# Rocket_End_Relays.net
KiCad netlist of a schematic drawn in EAGLE
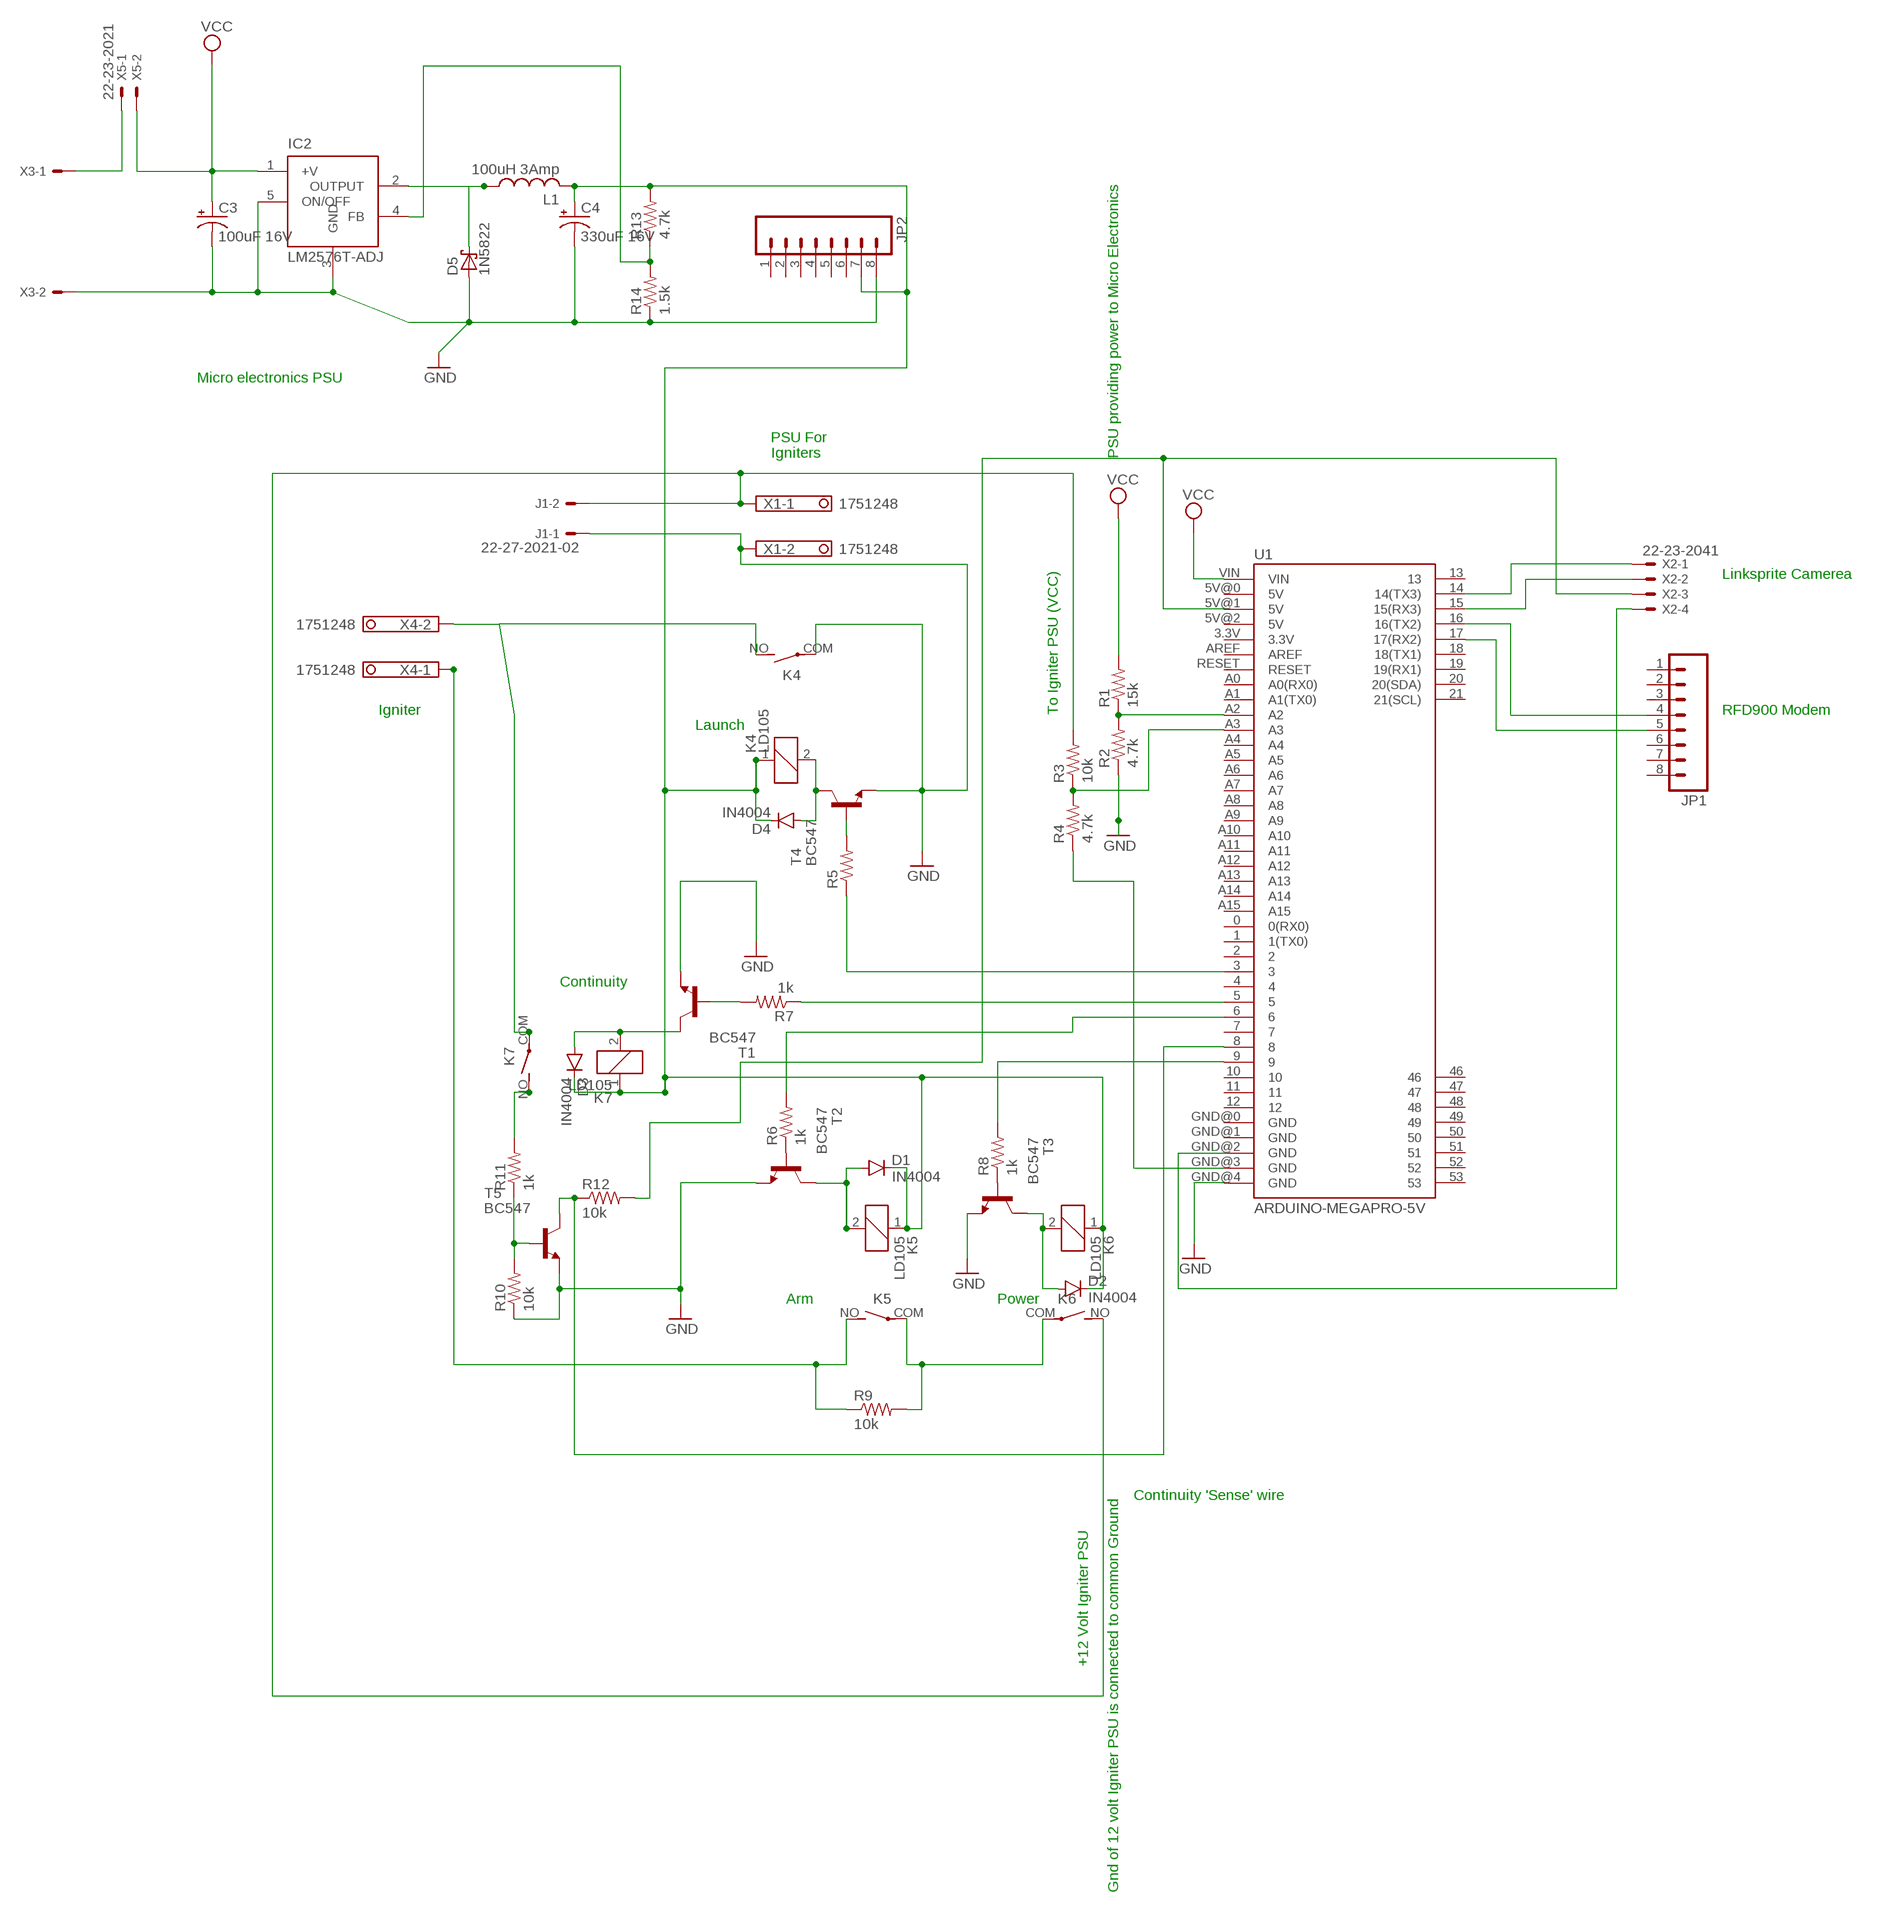
[diagram p0: schematic, sheet 1]

(export (version "E")
  (design (tool "Eeschema 10.0.6"))
  (components
    (comp (ref "C3")
      (value "100uF 16V")
      (footprint "eagle-import:E2-4")
      (libsource (lib "eagle-import") (part "CPOL-USE2-4"))
    )
    (comp (ref "C4")
      (value "330uF 16V")
      (footprint "eagle-import:E2-4")
      (libsource (lib "eagle-import") (part "CPOL-USE2-4"))
    )
    (comp (ref "D1")
      (value "IN4004")
      (footprint "eagle-import:DIODE-1N4148")
      (libsource (lib "eagle-import") (part "DIODE1N4148"))
    )
    (comp (ref "D2")
      (value "IN4004")
      (footprint "eagle-import:DIODE-1N4148")
      (libsource (lib "eagle-import") (part "DIODE1N4148"))
    )
    (comp (ref "D3")
      (value "IN4004")
      (footprint "eagle-import:DIODE-1N4148")
      (libsource (lib "eagle-import") (part "DIODE1N4148"))
    )
    (comp (ref "D4")
      (value "IN4004")
      (footprint "eagle-import:DIODE-1N4148")
      (libsource (lib "eagle-import") (part "DIODE1N4148"))
    )
    (comp (ref "D5")
      (value "1N5822")
      (footprint "eagle-import:C4111-15")
      (libsource (lib "eagle-import") (part "1N5908"))
    )
    (comp (ref "IC2")
      (value "LM2576T-ADJ")
      (footprint "eagle-import:TO220-5")
      (libsource (lib "eagle-import") (part "LM2576T-ADJ"))
    )
    (comp (ref "J1")
      (value "22-27-2021-02")
      (footprint "eagle-import:6410-02")
      (libsource (lib "eagle-import") (part "22-?-0227-2021"))
    )
    (comp (ref "JP1")
      (value "M08")
      (footprint "eagle-import:1X08_ROUND")
      (libsource (lib "eagle-import") (part "M08"))
    )
    (comp (ref "JP2")
      (value "M08")
      (footprint "eagle-import:1X08_ROUND")
      (libsource (lib "eagle-import") (part "M08"))
    )
    (comp (ref "K4")
      (value "LD105")
      (footprint "eagle-import:LD")
      (libsource (lib "eagle-import") (part "LD?105"))
    )
    (comp (ref "K5")
      (value "LD105")
      (footprint "eagle-import:LD")
      (libsource (lib "eagle-import") (part "LD?105"))
    )
    (comp (ref "K6")
      (value "LD105")
      (footprint "eagle-import:LD")
      (libsource (lib "eagle-import") (part "LD?105"))
    )
    (comp (ref "K7")
      (value "LD105")
      (footprint "eagle-import:LD")
      (libsource (lib "eagle-import") (part "LD?105"))
    )
    (comp (ref "L1")
      (value "100uH 3Amp")
      (footprint "eagle-import:TJ4-U1")
      (libsource (lib "eagle-import") (part "L-USTJ4-U1"))
    )
    (comp (ref "R1")
      (value "15k")
      (footprint "eagle-import:0204_7")
      (libsource (lib "eagle-import") (part "R-US_0204/7"))
    )
    (comp (ref "R2")
      (value "4.7k")
      (footprint "eagle-import:0204_7")
      (libsource (lib "eagle-import") (part "R-US_0204/7"))
    )
    (comp (ref "R3")
      (value "10k")
      (footprint "eagle-import:0204_7")
      (libsource (lib "eagle-import") (part "R-US_0204/7"))
    )
    (comp (ref "R4")
      (value "4.7k")
      (footprint "eagle-import:0204_7")
      (libsource (lib "eagle-import") (part "R-US_0204/7"))
    )
    (comp (ref "R5")
      (value "R-US_0204/7")
      (footprint "eagle-import:0204_7")
      (libsource (lib "eagle-import") (part "resistor_R-US_0204/7"))
    )
    (comp (ref "R6")
      (value "1k")
      (footprint "eagle-import:0204_7")
      (libsource (lib "eagle-import") (part "resistor_R-US_0204/7"))
    )
    (comp (ref "R7")
      (value "1k")
      (footprint "eagle-import:0204_7")
      (libsource (lib "eagle-import") (part "resistor_R-US_0204/7"))
    )
    (comp (ref "R8")
      (value "1k")
      (footprint "eagle-import:0204_7")
      (libsource (lib "eagle-import") (part "resistor_R-US_0204/7"))
    )
    (comp (ref "R9")
      (value "10k")
      (footprint "eagle-import:0204_7")
      (libsource (lib "eagle-import") (part "R-US_0204/7"))
    )
    (comp (ref "R10")
      (value "10k")
      (footprint "eagle-import:0207_7")
      (libsource (lib "eagle-import") (part "R-US_0207/7"))
    )
    (comp (ref "R11")
      (value "1k")
      (footprint "eagle-import:0207_12")
      (libsource (lib "eagle-import") (part "resistor_R-US_0207/12"))
    )
    (comp (ref "R12")
      (value "10k")
      (footprint "eagle-import:0204_7")
      (libsource (lib "eagle-import") (part "resistor_R-US_0204/7"))
    )
    (comp (ref "R13")
      (value "4.7k")
      (footprint "eagle-import:0204V")
      (libsource (lib "eagle-import") (part "resistor_R-US_0204/2V"))
    )
    (comp (ref "R14")
      (value "1.5k")
      (footprint "eagle-import:0207_7")
      (libsource (lib "eagle-import") (part "resistor_R-US_0207/7"))
    )
    (comp (ref "T1")
      (value "BC547")
      (footprint "eagle-import:TO92")
      (libsource (lib "eagle-import") (part "transistor-neu-to92_BC547"))
    )
    (comp (ref "T2")
      (value "BC547")
      (footprint "eagle-import:TO92")
      (libsource (lib "eagle-import") (part "transistor-neu-to92_BC547"))
    )
    (comp (ref "T3")
      (value "BC547")
      (footprint "eagle-import:TO92")
      (libsource (lib "eagle-import") (part "transistor-neu-to92_BC547"))
    )
    (comp (ref "T4")
      (value "BC547")
      (footprint "eagle-import:TO92")
      (libsource (lib "eagle-import") (part "transistor-neu-to92_BC547"))
    )
    (comp (ref "T5")
      (value "BC547")
      (footprint "eagle-import:TO92")
      (libsource (lib "eagle-import") (part "BC547"))
    )
    (comp (ref "U1")
      (value "ARDUINO-MEGAPRO-5V")
      (footprint "eagle-import:ARDUINO_MEGA-PRO-5V")
      (libsource (lib "eagle-import") (part "ARDUINO-MEGAPRO-5V"))
    )
    (comp (ref "X1")
      (value "1751248")
      (footprint "eagle-import:1751248")
      (libsource (lib "eagle-import") (part "1751248"))
    )
    (comp (ref "X2")
      (value "22-23-2041")
      (footprint "eagle-import:22-23-2041")
      (fields (field (name "MF") "MOLEX"))
      (libsource (lib "eagle-import") (part "22-23-2041"))
    )
    (comp (ref "X3")
      (value "22-23-2021")
      (footprint "eagle-import:22-23-2021")
      (fields (field (name "MF") "MOLEX"))
      (libsource (lib "eagle-import") (part "22-23-2021"))
    )
    (comp (ref "X4")
      (value "1751248")
      (footprint "eagle-import:1751248")
      (libsource (lib "eagle-import") (part "1751248"))
    )
    (comp (ref "X5")
      (value "22-23-2021")
      (footprint "eagle-import:22-23-2021")
      (fields (field (name "MF") "MOLEX"))
      (libsource (lib "eagle-import") (part "22-23-2021"))
    )
  )
  (nets
    (net (code "1") (name "GND") (class "Default")
      (node (ref "C3") (pin "-") (pinfunction "-_-") (pintype "passive"))
      (node (ref "C4") (pin "-") (pinfunction "-_-") (pintype "passive"))
      (node (ref "D5") (pin "A") (pinfunction "A_A") (pintype "passive"))
      (node (ref "IC2") (pin "3") (pinfunction "GND_3") (pintype "power_in"))
      (node (ref "IC2") (pin "5") (pinfunction "ON/OFF_5") (pintype "input"))
      (node (ref "J1") (pin "1") (pinfunction "S_1") (pintype "passive"))
      (node (ref "JP2") (pin "8") (pinfunction "8_8") (pintype "passive"))
      (node (ref "K4") (pin "COM") (pinfunction "P_COM") (pintype "passive"))
      (node (ref "R10") (pin "1") (pinfunction "1_1") (pintype "passive"))
      (node (ref "R14") (pin "1") (pinfunction "1_1") (pintype "passive"))
      (node (ref "R2") (pin "1") (pinfunction "1_1") (pintype "passive"))
      (node (ref "T1") (pin "1") (pinfunction "E_1") (pintype "passive"))
      (node (ref "T2") (pin "1") (pinfunction "E_1") (pintype "passive"))
      (node (ref "T3") (pin "1") (pinfunction "E_1") (pintype "passive"))
      (node (ref "T4") (pin "1") (pinfunction "E_1") (pintype "passive"))
      (node (ref "T5") (pin "1") (pinfunction "E_1") (pintype "passive"))
      (node (ref "U1") (pin "GND@4") (pinfunction "GND_GND@4") (pintype "bidirectional"))
      (node (ref "X1") (pin "2") (pinfunction "K_2") (pintype "passive"))
      (node (ref "X3") (pin "2") (pinfunction "S_2") (pintype "passive"))
    )
    (net (code "2") (name "Net-(C4-Pad+)") (class "Default")
      (node (ref "C4") (pin "+") (pinfunction "+_+") (pintype "passive"))
      (node (ref "D1") (pin "C") (pinfunction "C_C") (pintype "passive"))
      (node (ref "D2") (pin "C") (pinfunction "C_C") (pintype "passive"))
      (node (ref "D3") (pin "C") (pinfunction "C_C") (pintype "passive"))
      (node (ref "D4") (pin "C") (pinfunction "C_C") (pintype "passive"))
      (node (ref "JP2") (pin "7") (pinfunction "7_7") (pintype "passive"))
      (node (ref "K4") (pin "1") (pinfunction "1_1") (pintype "passive"))
      (node (ref "K5") (pin "1") (pinfunction "1_1") (pintype "passive"))
      (node (ref "K6") (pin "1") (pinfunction "1_1") (pintype "passive"))
      (node (ref "K7") (pin "1") (pinfunction "1_1") (pintype "passive"))
      (node (ref "L1") (pin "2") (pinfunction "2_2") (pintype "passive"))
      (node (ref "R13") (pin "2") (pinfunction "2_2") (pintype "passive"))
    )
    (net (code "3") (name "Net-(IC2-FB)") (class "Default")
      (node (ref "IC2") (pin "4") (pinfunction "FB_4") (pintype "input"))
      (node (ref "R13") (pin "1") (pinfunction "1_1") (pintype "passive"))
      (node (ref "R14") (pin "2") (pinfunction "2_2") (pintype "passive"))
    )
    (net (code "4") (name "Net-(IC2-OUTPUT)") (class "Default")
      (node (ref "D5") (pin "C") (pinfunction "C_C") (pintype "passive"))
      (node (ref "IC2") (pin "2") (pinfunction "OUTPUT_2") (pintype "output"))
      (node (ref "L1") (pin "1") (pinfunction "1_1") (pintype "passive"))
    )
    (net (code "5") (name "Net-(J1B-S)") (class "Default")
      (node (ref "J1") (pin "2") (pinfunction "S_2") (pintype "passive"))
      (node (ref "K6") (pin "NO") (pinfunction "S_NO") (pintype "passive"))
      (node (ref "R3") (pin "2") (pinfunction "2_2") (pintype "passive"))
      (node (ref "X1") (pin "1") (pinfunction "K_1") (pintype "passive"))
    )
    (net (code "6") (name "Net-(K4B-S)") (class "Default")
      (node (ref "K4") (pin "NO") (pinfunction "S_NO") (pintype "passive"))
      (node (ref "K7") (pin "COM") (pinfunction "P_COM") (pintype "passive"))
      (node (ref "X4") (pin "2") (pinfunction "K_2") (pintype "passive"))
    )
    (net (code "7") (name "Net-(K5B-P)") (class "Default")
      (node (ref "K5") (pin "COM") (pinfunction "P_COM") (pintype "passive"))
      (node (ref "K6") (pin "COM") (pinfunction "P_COM") (pintype "passive"))
      (node (ref "R9") (pin "2") (pinfunction "2_2") (pintype "passive"))
    )
    (net (code "8") (name "Net-(K5B-S)") (class "Default")
      (node (ref "K5") (pin "NO") (pinfunction "S_NO") (pintype "passive"))
      (node (ref "R9") (pin "1") (pinfunction "1_1") (pintype "passive"))
      (node (ref "X4") (pin "1") (pinfunction "K_1") (pintype "passive"))
    )
    (net (code "9") (name "Net-(K7B-S)") (class "Default")
      (node (ref "K7") (pin "NO") (pinfunction "S_NO") (pintype "passive"))
      (node (ref "R11") (pin "2") (pinfunction "2_2") (pintype "passive"))
    )
    (net (code "10") (name "Net-(R1-Pad1)") (class "Default")
      (node (ref "R1") (pin "1") (pinfunction "1_1") (pintype "passive"))
      (node (ref "R2") (pin "2") (pinfunction "2_2") (pintype "passive"))
      (node (ref "U1") (pin "A2") (pinfunction "A2_A2") (pintype "bidirectional"))
    )
    (net (code "11") (name "Net-(R3-Pad1)") (class "Default")
      (node (ref "R3") (pin "1") (pinfunction "1_1") (pintype "passive"))
      (node (ref "R4") (pin "2") (pinfunction "2_2") (pintype "passive"))
      (node (ref "U1") (pin "A3") (pinfunction "A3_A3") (pintype "bidirectional"))
    )
    (net (code "12") (name "Net-(R4-Pad1)") (class "Default")
      (node (ref "R4") (pin "1") (pinfunction "1_1") (pintype "passive"))
      (node (ref "U1") (pin "GND@3") (pinfunction "GND_GND@3") (pintype "bidirectional"))
    )
    (net (code "13") (name "Net-(R5-Pad1)") (class "Default")
      (node (ref "R5") (pin "1") (pinfunction "1_1") (pintype "passive"))
      (node (ref "U1") (pin "3") (pinfunction "3_3") (pintype "bidirectional"))
    )
    (net (code "14") (name "Net-(R6-Pad2)") (class "Default")
      (node (ref "R6") (pin "2") (pinfunction "2_2") (pintype "passive"))
      (node (ref "U1") (pin "6") (pinfunction "6_6") (pintype "bidirectional"))
    )
    (net (code "15") (name "Net-(R7-Pad1)") (class "Default")
      (node (ref "R7") (pin "1") (pinfunction "1_1") (pintype "passive"))
      (node (ref "U1") (pin "5") (pinfunction "5_5") (pintype "bidirectional"))
    )
    (net (code "16") (name "Net-(R8-Pad2)") (class "Default")
      (node (ref "R8") (pin "2") (pinfunction "2_2") (pintype "passive"))
      (node (ref "U1") (pin "9") (pinfunction "9_9") (pintype "bidirectional"))
    )
    (net (code "17") (name "Net-(T1-B)") (class "Default")
      (node (ref "R7") (pin "2") (pinfunction "2_2") (pintype "passive"))
      (node (ref "T1") (pin "2") (pinfunction "B_2") (pintype "passive"))
    )
    (net (code "18") (name "Net-(T1-C)") (class "Default")
      (node (ref "D3") (pin "A") (pinfunction "A_A") (pintype "passive"))
      (node (ref "K7") (pin "2") (pinfunction "2_2") (pintype "passive"))
      (node (ref "T1") (pin "3") (pinfunction "C_3") (pintype "passive"))
    )
    (net (code "19") (name "Net-(T2-B)") (class "Default")
      (node (ref "R6") (pin "1") (pinfunction "1_1") (pintype "passive"))
      (node (ref "T2") (pin "2") (pinfunction "B_2") (pintype "passive"))
    )
    (net (code "20") (name "Net-(T2-C)") (class "Default")
      (node (ref "D1") (pin "A") (pinfunction "A_A") (pintype "passive"))
      (node (ref "K5") (pin "2") (pinfunction "2_2") (pintype "passive"))
      (node (ref "T2") (pin "3") (pinfunction "C_3") (pintype "passive"))
    )
    (net (code "21") (name "Net-(T3-B)") (class "Default")
      (node (ref "R8") (pin "1") (pinfunction "1_1") (pintype "passive"))
      (node (ref "T3") (pin "2") (pinfunction "B_2") (pintype "passive"))
    )
    (net (code "22") (name "Net-(T3-C)") (class "Default")
      (node (ref "D2") (pin "A") (pinfunction "A_A") (pintype "passive"))
      (node (ref "K6") (pin "2") (pinfunction "2_2") (pintype "passive"))
      (node (ref "T3") (pin "3") (pinfunction "C_3") (pintype "passive"))
    )
    (net (code "23") (name "Net-(T4-B)") (class "Default")
      (node (ref "R5") (pin "2") (pinfunction "2_2") (pintype "passive"))
      (node (ref "T4") (pin "2") (pinfunction "B_2") (pintype "passive"))
    )
    (net (code "24") (name "Net-(T4-C)") (class "Default")
      (node (ref "D4") (pin "A") (pinfunction "A_A") (pintype "passive"))
      (node (ref "K4") (pin "2") (pinfunction "2_2") (pintype "passive"))
      (node (ref "T4") (pin "3") (pinfunction "C_3") (pintype "passive"))
    )
    (net (code "25") (name "Net-(T5-B)") (class "Default")
      (node (ref "R10") (pin "2") (pinfunction "2_2") (pintype "passive"))
      (node (ref "R11") (pin "1") (pinfunction "1_1") (pintype "passive"))
      (node (ref "T5") (pin "2") (pinfunction "B_2") (pintype "passive"))
    )
    (net (code "26") (name "Net-(T5-C)") (class "Default")
      (node (ref "R12") (pin "1") (pinfunction "1_1") (pintype "passive"))
      (node (ref "T5") (pin "3") (pinfunction "C_3") (pintype "passive"))
      (node (ref "U1") (pin "8") (pinfunction "8_8") (pintype "bidirectional"))
    )
    (net (code "27") (name "Net-(U1-14(TX3))") (class "Default")
      (node (ref "U1") (pin "14") (pinfunction "14(TX3)_14") (pintype "bidirectional"))
      (node (ref "X2") (pin "1") (pinfunction "S_1") (pintype "passive"))
    )
    (net (code "28") (name "Net-(U1-15(RX3))") (class "Default")
      (node (ref "U1") (pin "15") (pinfunction "15(RX3)_15") (pintype "bidirectional"))
      (node (ref "X2") (pin "2") (pinfunction "S_2") (pintype "passive"))
    )
    (net (code "29") (name "Net-(U1-16(TX2))") (class "Default")
      (node (ref "JP1") (pin "4") (pinfunction "4_4") (pintype "passive"))
      (node (ref "U1") (pin "16") (pinfunction "16(TX2)_16") (pintype "bidirectional"))
    )
    (net (code "30") (name "Net-(U1-17(RX2))") (class "Default")
      (node (ref "JP1") (pin "5") (pinfunction "5_5") (pintype "passive"))
      (node (ref "U1") (pin "17") (pinfunction "17(RX2)_17") (pintype "bidirectional"))
    )
    (net (code "31") (name "Net-(X2C-S)") (class "Default")
      (node (ref "R12") (pin "2") (pinfunction "2_2") (pintype "passive"))
      (node (ref "U1") (pin "5V@1") (pinfunction "5V_5V@1") (pintype "bidirectional"))
      (node (ref "X2") (pin "3") (pinfunction "S_3") (pintype "passive"))
    )
    (net (code "32") (name "Net-(X2D-S)") (class "Default")
      (node (ref "U1") (pin "GND@2") (pinfunction "GND_GND@2") (pintype "bidirectional"))
      (node (ref "X2") (pin "4") (pinfunction "S_4") (pintype "passive"))
    )
    (net (code "33") (name "Net-(X3A-S)") (class "Default")
      (node (ref "X3") (pin "1") (pinfunction "S_1") (pintype "passive"))
      (node (ref "X5") (pin "1") (pinfunction "S_1") (pintype "passive"))
    )
    (net (code "34") (name "VCC") (class "Default")
      (node (ref "C3") (pin "+") (pinfunction "+_+") (pintype "passive"))
      (node (ref "IC2") (pin "1") (pinfunction "+V_1") (pintype "power_in"))
      (node (ref "R1") (pin "2") (pinfunction "2_2") (pintype "passive"))
      (node (ref "U1") (pin "VIN") (pinfunction "VIN_VIN") (pintype "bidirectional"))
      (node (ref "X5") (pin "2") (pinfunction "S_2") (pintype "passive"))
    )
    (net (code "35") (name "unconnected-(JP1-Pad1)") (class "Default")
      (node (ref "JP1") (pin "1") (pinfunction "1_1") (pintype "passive"))
    )
    (net (code "36") (name "unconnected-(JP1-Pad2)") (class "Default")
      (node (ref "JP1") (pin "2") (pinfunction "2_2") (pintype "passive"))
    )
    (net (code "37") (name "unconnected-(JP1-Pad3)") (class "Default")
      (node (ref "JP1") (pin "3") (pinfunction "3_3") (pintype "passive"))
    )
    (net (code "38") (name "unconnected-(JP1-Pad6)") (class "Default")
      (node (ref "JP1") (pin "6") (pinfunction "6_6") (pintype "passive"))
    )
    (net (code "39") (name "unconnected-(JP1-Pad7)") (class "Default")
      (node (ref "JP1") (pin "7") (pinfunction "7_7") (pintype "passive"))
    )
    (net (code "40") (name "unconnected-(JP1-Pad8)") (class "Default")
      (node (ref "JP1") (pin "8") (pinfunction "8_8") (pintype "passive"))
    )
    (net (code "41") (name "unconnected-(JP2-Pad1)") (class "Default")
      (node (ref "JP2") (pin "1") (pinfunction "1_1") (pintype "passive"))
    )
    (net (code "42") (name "unconnected-(JP2-Pad2)") (class "Default")
      (node (ref "JP2") (pin "2") (pinfunction "2_2") (pintype "passive"))
    )
    (net (code "43") (name "unconnected-(JP2-Pad3)") (class "Default")
      (node (ref "JP2") (pin "3") (pinfunction "3_3") (pintype "passive"))
    )
    (net (code "44") (name "unconnected-(JP2-Pad4)") (class "Default")
      (node (ref "JP2") (pin "4") (pinfunction "4_4") (pintype "passive"))
    )
    (net (code "45") (name "unconnected-(JP2-Pad5)") (class "Default")
      (node (ref "JP2") (pin "5") (pinfunction "5_5") (pintype "passive"))
    )
    (net (code "46") (name "unconnected-(JP2-Pad6)") (class "Default")
      (node (ref "JP2") (pin "6") (pinfunction "6_6") (pintype "passive"))
    )
    (net (code "47") (name "unconnected-(U1-0(RX0)-Pad0)") (class "Default")
      (node (ref "U1") (pin "0") (pinfunction "0(RX0)_0") (pintype "bidirectional"))
    )
    (net (code "48") (name "unconnected-(U1-1(TX0)-Pad1)") (class "Default")
      (node (ref "U1") (pin "1") (pinfunction "1(TX0)_1") (pintype "bidirectional"))
    )
    (net (code "49") (name "unconnected-(U1-5V-Pad5V@0)") (class "Default")
      (node (ref "U1") (pin "5V@0") (pinfunction "5V_5V@0") (pintype "bidirectional"))
    )
    (net (code "50") (name "unconnected-(U1-5V-Pad5V@2)") (class "Default")
      (node (ref "U1") (pin "5V@2") (pinfunction "5V_5V@2") (pintype "bidirectional"))
    )
    (net (code "51") (name "unconnected-(U1-18(TX1)-Pad18)") (class "Default")
      (node (ref "U1") (pin "18") (pinfunction "18(TX1)_18") (pintype "bidirectional"))
    )
    (net (code "52") (name "unconnected-(U1-19(RX1)-Pad19)") (class "Default")
      (node (ref "U1") (pin "19") (pinfunction "19(RX1)_19") (pintype "bidirectional"))
    )
    (net (code "53") (name "unconnected-(U1-20(SDA)-Pad20)") (class "Default")
      (node (ref "U1") (pin "20") (pinfunction "20(SDA)_20") (pintype "bidirectional"))
    )
    (net (code "54") (name "unconnected-(U1-21(SCL)-Pad21)") (class "Default")
      (node (ref "U1") (pin "21") (pinfunction "21(SCL)_21") (pintype "bidirectional"))
    )
    (net (code "55") (name "unconnected-(U1-A0(RX0)-PadA0)") (class "Default")
      (node (ref "U1") (pin "A0") (pinfunction "A0(RX0)_A0") (pintype "bidirectional"))
    )
    (net (code "56") (name "unconnected-(U1-A1(TX0)-PadA1)") (class "Default")
      (node (ref "U1") (pin "A1") (pinfunction "A1(TX0)_A1") (pintype "bidirectional"))
    )
    (net (code "57") (name "unconnected-(U1-GND-PadGND@0)") (class "Default")
      (node (ref "U1") (pin "GND@0") (pinfunction "GND_GND@0") (pintype "bidirectional"))
    )
    (net (code "58") (name "unconnected-(U1-GND-PadGND@1)") (class "Default")
      (node (ref "U1") (pin "GND@1") (pinfunction "GND_GND@1") (pintype "bidirectional"))
    )
    (net (code "59") (name "unconnected-(U1-Pad2)") (class "Default")
      (node (ref "U1") (pin "2") (pinfunction "2_2") (pintype "bidirectional"))
    )
    (net (code "60") (name "unconnected-(U1-Pad3.3V)") (class "Default")
      (node (ref "U1") (pin "3.3V") (pinfunction "3.3V_3.3V") (pintype "bidirectional"))
    )
    (net (code "61") (name "unconnected-(U1-Pad4)") (class "Default")
      (node (ref "U1") (pin "4") (pinfunction "4_4") (pintype "bidirectional"))
    )
    (net (code "62") (name "unconnected-(U1-Pad7)") (class "Default")
      (node (ref "U1") (pin "7") (pinfunction "7_7") (pintype "bidirectional"))
    )
    (net (code "63") (name "unconnected-(U1-Pad10)") (class "Default")
      (node (ref "U1") (pin "10") (pinfunction "10_10") (pintype "bidirectional"))
    )
    (net (code "64") (name "unconnected-(U1-Pad11)") (class "Default")
      (node (ref "U1") (pin "11") (pinfunction "11_11") (pintype "bidirectional"))
    )
    (net (code "65") (name "unconnected-(U1-Pad12)") (class "Default")
      (node (ref "U1") (pin "12") (pinfunction "12_12") (pintype "bidirectional"))
    )
    (net (code "66") (name "unconnected-(U1-Pad13)") (class "Default")
      (node (ref "U1") (pin "13") (pinfunction "13_13") (pintype "bidirectional"))
    )
    (net (code "67") (name "unconnected-(U1-Pad46)") (class "Default")
      (node (ref "U1") (pin "46") (pinfunction "46_46") (pintype "bidirectional"))
    )
    (net (code "68") (name "unconnected-(U1-Pad47)") (class "Default")
      (node (ref "U1") (pin "47") (pinfunction "47_47") (pintype "bidirectional"))
    )
    (net (code "69") (name "unconnected-(U1-Pad48)") (class "Default")
      (node (ref "U1") (pin "48") (pinfunction "48_48") (pintype "bidirectional"))
    )
    (net (code "70") (name "unconnected-(U1-Pad49)") (class "Default")
      (node (ref "U1") (pin "49") (pinfunction "49_49") (pintype "bidirectional"))
    )
    (net (code "71") (name "unconnected-(U1-Pad50)") (class "Default")
      (node (ref "U1") (pin "50") (pinfunction "50_50") (pintype "bidirectional"))
    )
    (net (code "72") (name "unconnected-(U1-Pad51)") (class "Default")
      (node (ref "U1") (pin "51") (pinfunction "51_51") (pintype "bidirectional"))
    )
    (net (code "73") (name "unconnected-(U1-Pad52)") (class "Default")
      (node (ref "U1") (pin "52") (pinfunction "52_52") (pintype "bidirectional"))
    )
    (net (code "74") (name "unconnected-(U1-Pad53)") (class "Default")
      (node (ref "U1") (pin "53") (pinfunction "53_53") (pintype "bidirectional"))
    )
    (net (code "75") (name "unconnected-(U1-PadA4)") (class "Default")
      (node (ref "U1") (pin "A4") (pinfunction "A4_A4") (pintype "bidirectional"))
    )
    (net (code "76") (name "unconnected-(U1-PadA5)") (class "Default")
      (node (ref "U1") (pin "A5") (pinfunction "A5_A5") (pintype "bidirectional"))
    )
    (net (code "77") (name "unconnected-(U1-PadA6)") (class "Default")
      (node (ref "U1") (pin "A6") (pinfunction "A6_A6") (pintype "bidirectional"))
    )
    (net (code "78") (name "unconnected-(U1-PadA7)") (class "Default")
      (node (ref "U1") (pin "A7") (pinfunction "A7_A7") (pintype "bidirectional"))
    )
    (net (code "79") (name "unconnected-(U1-PadA8)") (class "Default")
      (node (ref "U1") (pin "A8") (pinfunction "A8_A8") (pintype "bidirectional"))
    )
    (net (code "80") (name "unconnected-(U1-PadA9)") (class "Default")
      (node (ref "U1") (pin "A9") (pinfunction "A9_A9") (pintype "bidirectional"))
    )
    (net (code "81") (name "unconnected-(U1-PadA10)") (class "Default")
      (node (ref "U1") (pin "A10") (pinfunction "A10_A10") (pintype "bidirectional"))
    )
    (net (code "82") (name "unconnected-(U1-PadA11)") (class "Default")
      (node (ref "U1") (pin "A11") (pinfunction "A11_A11") (pintype "bidirectional"))
    )
    (net (code "83") (name "unconnected-(U1-PadA12)") (class "Default")
      (node (ref "U1") (pin "A12") (pinfunction "A12_A12") (pintype "bidirectional"))
    )
    (net (code "84") (name "unconnected-(U1-PadA13)") (class "Default")
      (node (ref "U1") (pin "A13") (pinfunction "A13_A13") (pintype "bidirectional"))
    )
    (net (code "85") (name "unconnected-(U1-PadA14)") (class "Default")
      (node (ref "U1") (pin "A14") (pinfunction "A14_A14") (pintype "bidirectional"))
    )
    (net (code "86") (name "unconnected-(U1-PadA15)") (class "Default")
      (node (ref "U1") (pin "A15") (pinfunction "A15_A15") (pintype "bidirectional"))
    )
    (net (code "87") (name "unconnected-(U1-PadAREF)") (class "Default")
      (node (ref "U1") (pin "AREF") (pinfunction "AREF_AREF") (pintype "bidirectional"))
    )
    (net (code "88") (name "unconnected-(U1-PadRESET)") (class "Default")
      (node (ref "U1") (pin "RESET") (pinfunction "RESET_RESET") (pintype "bidirectional"))
    )
  )
)
